# Seeeduino_LoRaWan.net
KiCad netlist of a schematic drawn in EAGLE
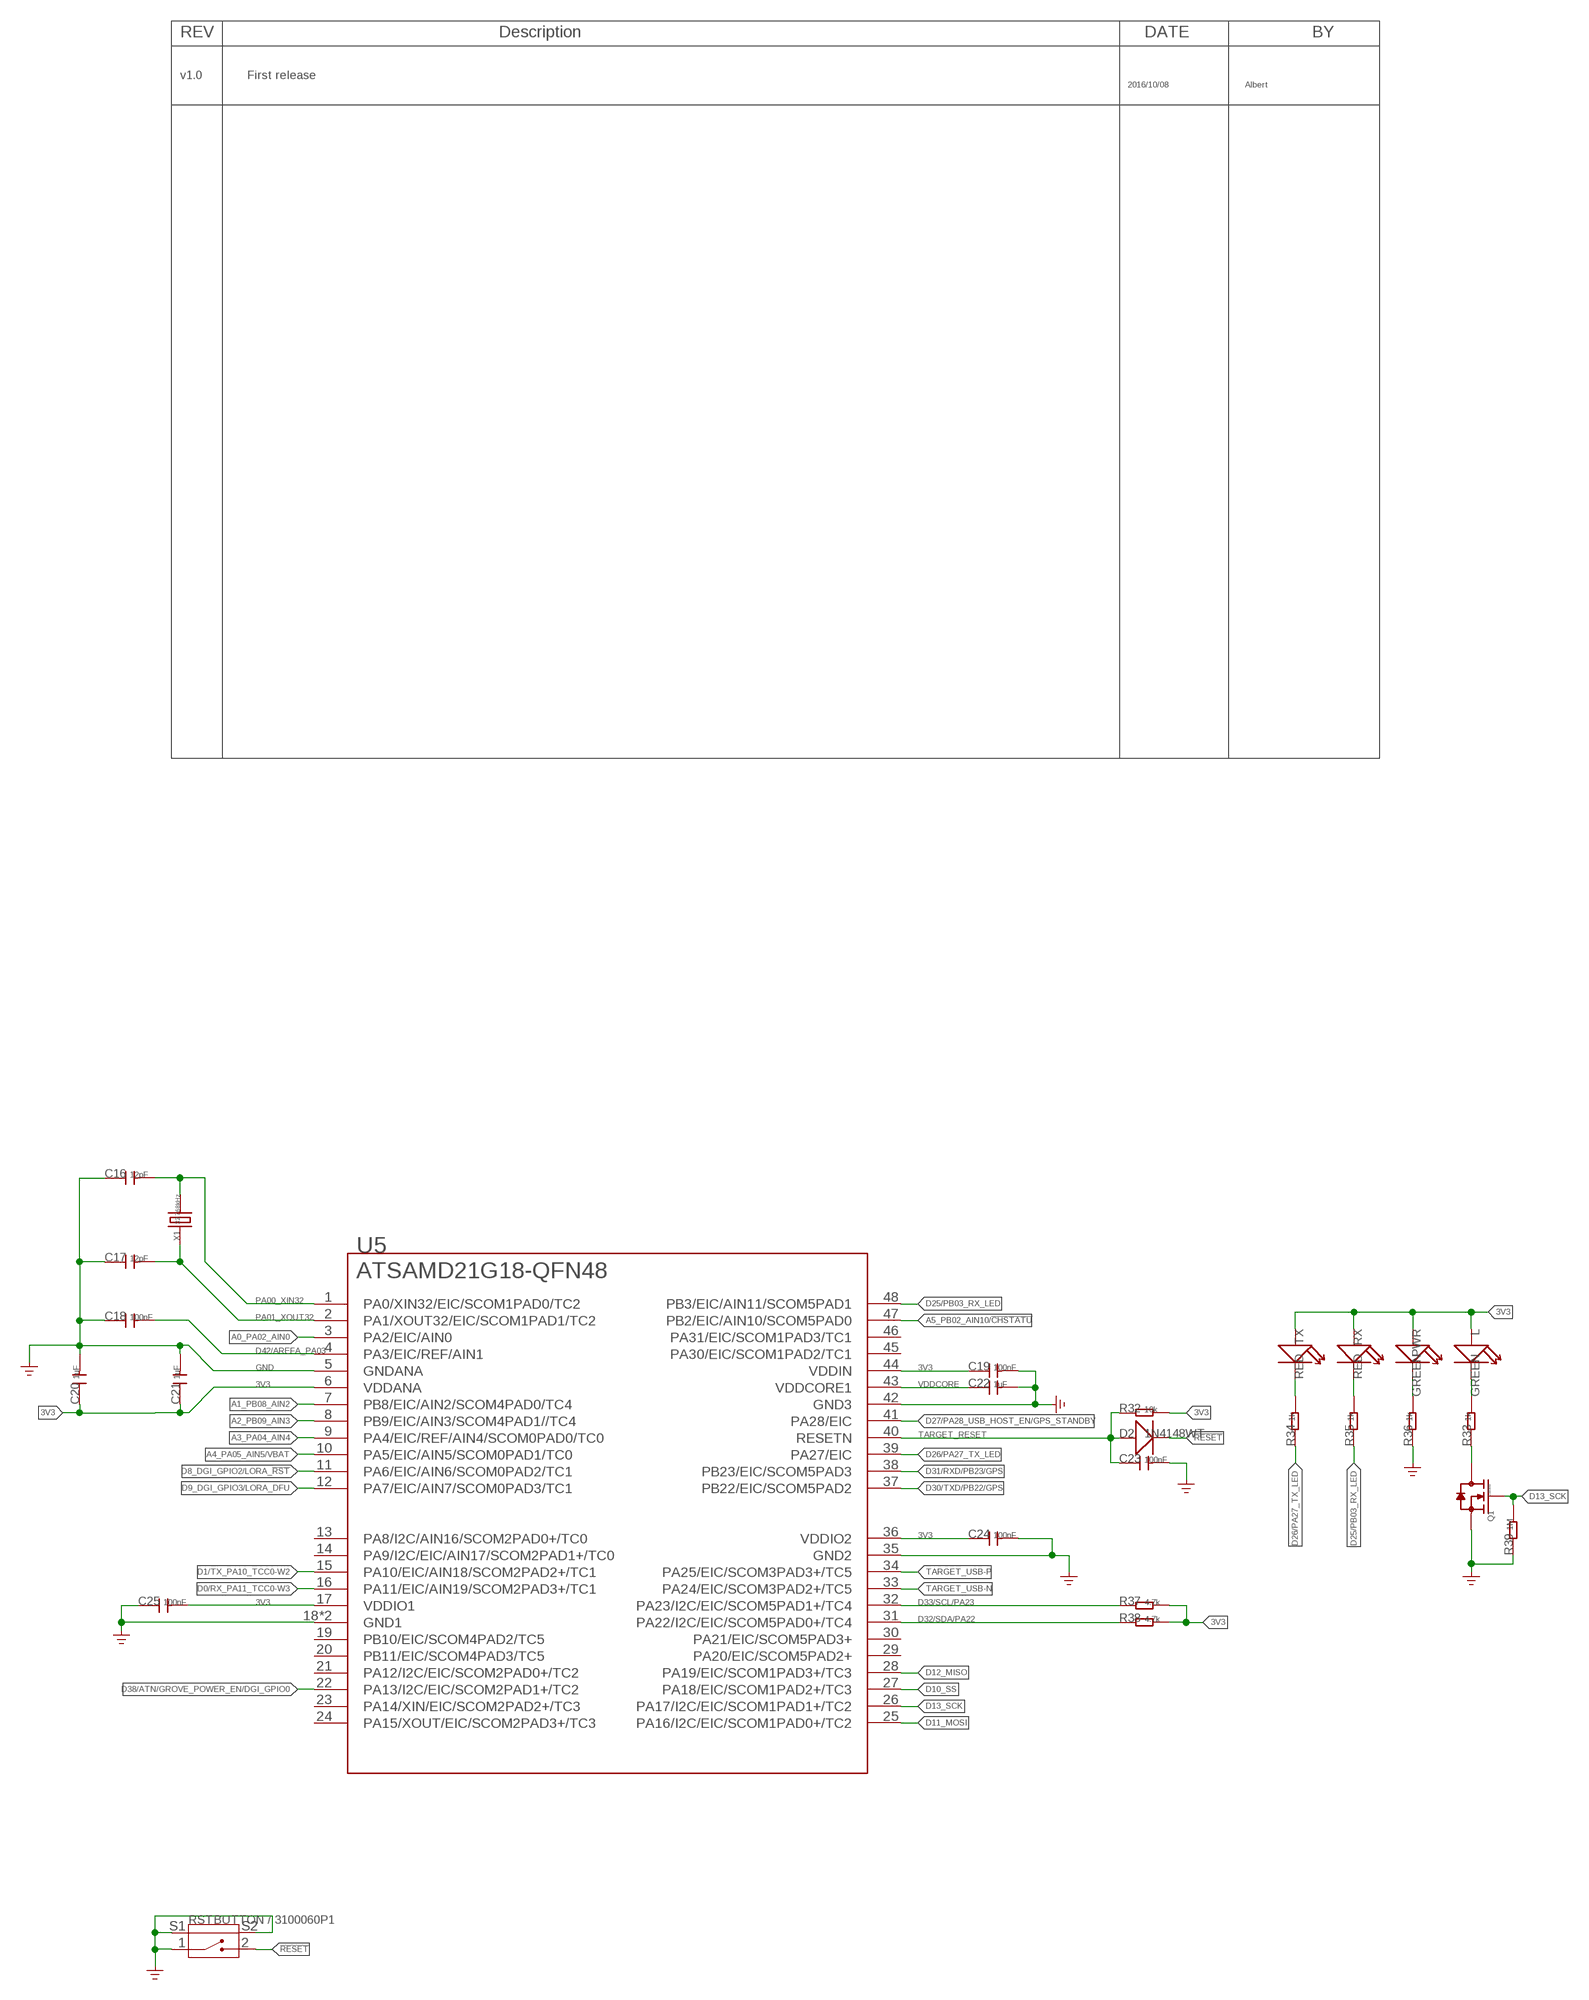
[diagram p0: schematic, sheet 1, part 1 of 2]
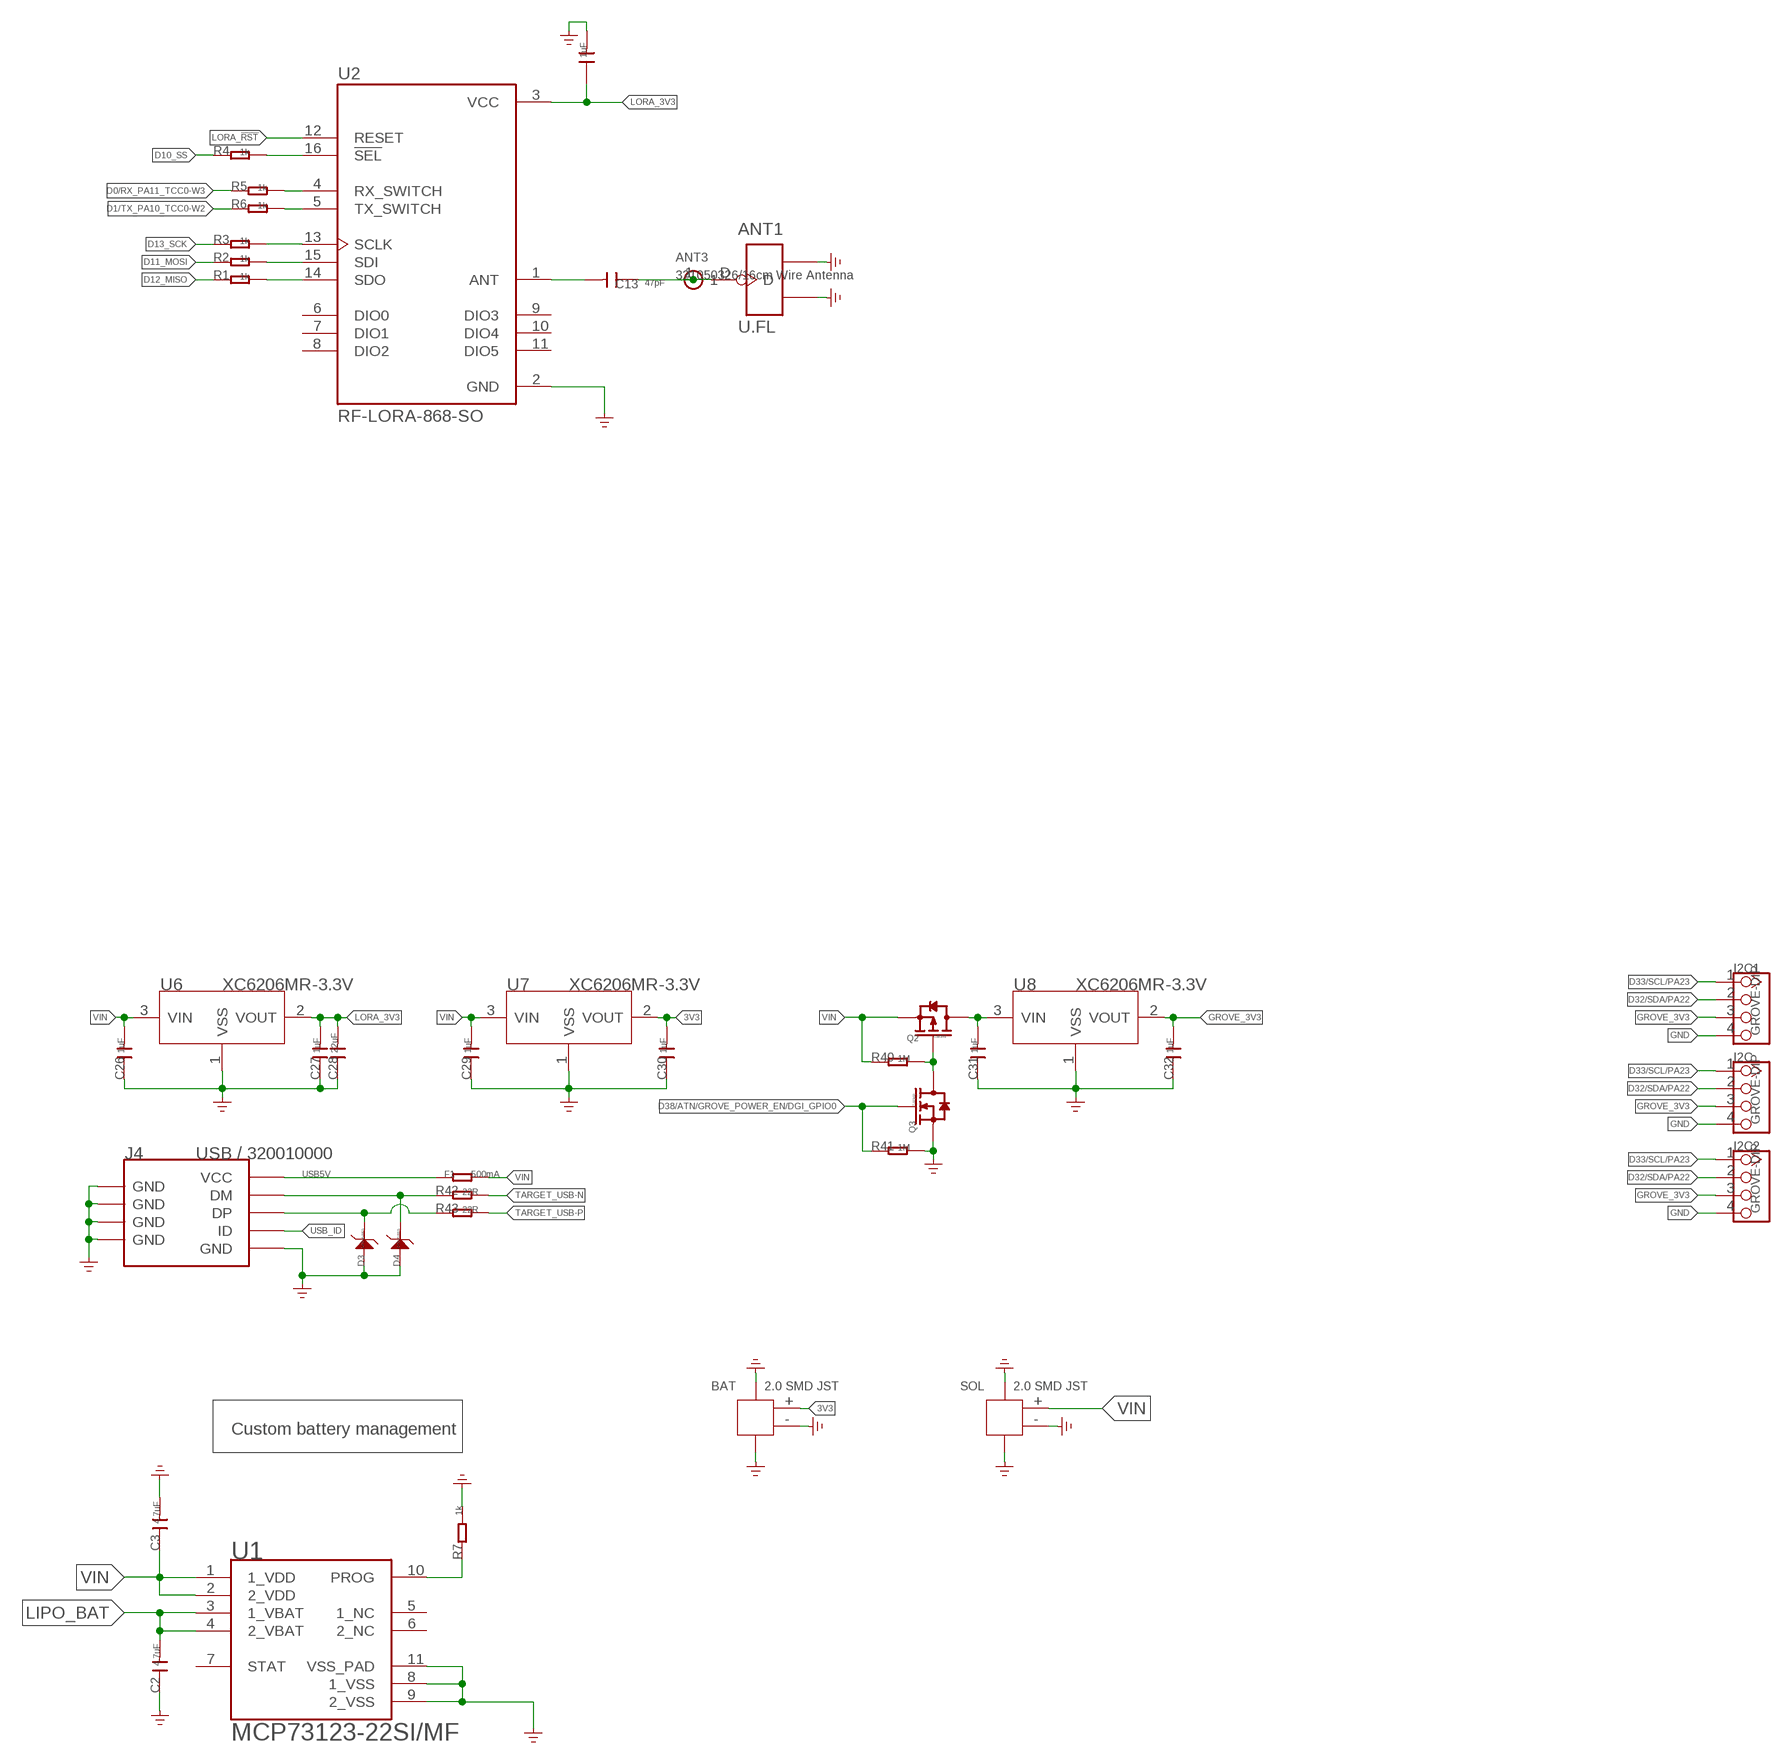
[diagram p1: schematic, sheet 1, part 2 of 2]

(export (version "E")
  (design (tool "Eeschema 10.0.6"))
  (components
    (comp (ref "ANT1")
      (value "U.FL")
      (footprint "eagle-import:U-FL3P-SMD-2.6X2.6X1.0MM")
      (libsource (lib "eagle-import") (part "ANTENNA-U-FL"))
    )
    (comp (ref "ANT3")
      (value "321050326/16cm Wire Antenna")
      (footprint "eagle-import:1P-65_35MIL")
      (libsource (lib "eagle-import") (part "HEADER-1P-35"))
    )
    (comp (ref "BAT")
      (value "2.0 SMD JST")
      (footprint "eagle-import:HW2-SMD-2.0-90D")
      (libsource (lib "eagle-import") (part "JST-2P-SMD'2.0'"))
    )
    (comp (ref "C1")
      (value "1uF")
      (footprint "eagle-import:C0603")
      (libsource (lib "eagle-import") (part "C-0603"))
    )
    (comp (ref "C2")
      (value "4.7uF")
      (footprint "eagle-import:C0603")
      (libsource (lib "eagle-import") (part "C-0603"))
    )
    (comp (ref "C3")
      (value "4.7uF")
      (footprint "eagle-import:C0603")
      (libsource (lib "eagle-import") (part "C-0603"))
    )
    (comp (ref "C13")
      (value "47pF")
      (footprint "eagle-import:C0603")
      (libsource (lib "eagle-import") (part "C-0603"))
    )
    (comp (ref "C16")
      (value "12pF")
      (footprint "eagle-import:C0603")
      (libsource (lib "eagle-import") (part "C-0603"))
    )
    (comp (ref "C17")
      (value "12pF")
      (footprint "eagle-import:C0603")
      (libsource (lib "eagle-import") (part "C-0603"))
    )
    (comp (ref "C18")
      (value "100nF")
      (footprint "eagle-import:C0603")
      (libsource (lib "eagle-import") (part "C-0603"))
    )
    (comp (ref "C19")
      (value "100nF")
      (footprint "eagle-import:C0603")
      (libsource (lib "eagle-import") (part "C-0603"))
    )
    (comp (ref "C20")
      (value "1uF")
      (footprint "eagle-import:C0603")
      (libsource (lib "eagle-import") (part "C-0603"))
    )
    (comp (ref "C21")
      (value "1uF")
      (footprint "eagle-import:C0603")
      (libsource (lib "eagle-import") (part "C-0603"))
    )
    (comp (ref "C22")
      (value "1uF")
      (footprint "eagle-import:C0603")
      (libsource (lib "eagle-import") (part "C-0603"))
    )
    (comp (ref "C23")
      (value "100nF")
      (footprint "eagle-import:C0603")
      (libsource (lib "eagle-import") (part "C-0603"))
    )
    (comp (ref "C24")
      (value "100nF")
      (footprint "eagle-import:C0603")
      (libsource (lib "eagle-import") (part "C-0603"))
    )
    (comp (ref "C25")
      (value "100nF")
      (footprint "eagle-import:C0603")
      (libsource (lib "eagle-import") (part "C-0603"))
    )
    (comp (ref "C26")
      (value "1uF")
      (footprint "eagle-import:C0603")
      (libsource (lib "eagle-import") (part "C-0603"))
    )
    (comp (ref "C27")
      (value "1uF")
      (footprint "eagle-import:C0603")
      (libsource (lib "eagle-import") (part "C-0603"))
    )
    (comp (ref "C28")
      (value "22uF")
      (footprint "eagle-import:C0603")
      (libsource (lib "eagle-import") (part "C-0603"))
    )
    (comp (ref "C29")
      (value "1uF")
      (footprint "eagle-import:C0603")
      (libsource (lib "eagle-import") (part "C-0603"))
    )
    (comp (ref "C30")
      (value "1uF")
      (footprint "eagle-import:C0603")
      (libsource (lib "eagle-import") (part "C-0603"))
    )
    (comp (ref "C31")
      (value "1uF")
      (footprint "eagle-import:C0603")
      (libsource (lib "eagle-import") (part "C-0603"))
    )
    (comp (ref "C32")
      (value "1uF")
      (footprint "eagle-import:C0603")
      (libsource (lib "eagle-import") (part "C-0603"))
    )
    (comp (ref "D2")
      (value "1N4148WT")
      (footprint "eagle-import:SOD523")
      (libsource (lib "eagle-import") (part "D'0603'"))
    )
    (comp (ref "D3")
      (value "DF2S6.8FS")
      (footprint "eagle-import:SOD-923")
      (libsource (lib "eagle-import") (part "D-ESD-2P'DF2S6.8FS'"))
    )
    (comp (ref "D4")
      (value "DF2S6.8FS")
      (footprint "eagle-import:SOD-923")
      (libsource (lib "eagle-import") (part "D-ESD-2P'DF2S6.8FS'"))
    )
    (comp (ref "F1")
      (value "500mA")
      (footprint "eagle-import:R0603")
      (libsource (lib "eagle-import") (part "Discrete-smallsmall_R-0603"))
    )
    (comp (ref "I2C")
      (value "GROVE-DIP")
      (footprint "eagle-import:4P-2.0")
      (libsource (lib "eagle-import") (part "TWIG-4P-2.0-2.0"))
    )
    (comp (ref "I2C1")
      (value "GROVE-DIP")
      (footprint "eagle-import:4P-2.0")
      (libsource (lib "eagle-import") (part "TWIG-4P-2.0-2.0"))
    )
    (comp (ref "I2C2")
      (value "GROVE-DIP")
      (footprint "eagle-import:4P-2.0")
      (libsource (lib "eagle-import") (part "TWIG-4P-2.0-2.0"))
    )
    (comp (ref "J4")
      (value "USB / 320010000")
      (footprint "eagle-import:MICRO-USB")
      (libsource (lib "eagle-import") (part "USB-MINIUSB-5P-MICRO"))
    )
    (comp (ref "L")
      (value "GREEN")
      (footprint "eagle-import:LED-0603")
      (libsource (lib "eagle-import") (part "LED'0603'"))
    )
    (comp (ref "PWR")
      (value "GREEN")
      (footprint "eagle-import:LED-0603")
      (libsource (lib "eagle-import") (part "LED'0603'"))
    )
    (comp (ref "Q1")
      (value "CJ2102")
      (footprint "eagle-import:SOT-323")
      (libsource (lib "eagle-import") (part "MOSFET-N'SI1304BDL'"))
    )
    (comp (ref "Q2")
      (value "CJ2101")
      (footprint "eagle-import:SOT323")
      (libsource (lib "eagle-import") (part "MOSFET-P-SOT323"))
    )
    (comp (ref "Q3")
      (value "CJ2102")
      (footprint "eagle-import:SOT-323")
      (libsource (lib "eagle-import") (part "MOSFET-N'SI1304BDL'"))
    )
    (comp (ref "R1")
      (value "1k")
      (footprint "eagle-import:R0603")
      (libsource (lib "eagle-import") (part "R-0603"))
    )
    (comp (ref "R2")
      (value "1k")
      (footprint "eagle-import:R0603")
      (libsource (lib "eagle-import") (part "R-0603"))
    )
    (comp (ref "R3")
      (value "1k")
      (footprint "eagle-import:R0603")
      (libsource (lib "eagle-import") (part "R-0603"))
    )
    (comp (ref "R4")
      (value "1k")
      (footprint "eagle-import:R0603")
      (libsource (lib "eagle-import") (part "R-0603"))
    )
    (comp (ref "R5")
      (value "1k")
      (footprint "eagle-import:R0603")
      (libsource (lib "eagle-import") (part "R-0603"))
    )
    (comp (ref "R6")
      (value "1k")
      (footprint "eagle-import:R0603")
      (libsource (lib "eagle-import") (part "R-0603"))
    )
    (comp (ref "R7")
      (value "1k")
      (footprint "eagle-import:R0603")
      (libsource (lib "eagle-import") (part "R-0603"))
    )
    (comp (ref "R32")
      (value "10k")
      (footprint "eagle-import:R0603")
      (libsource (lib "eagle-import") (part "R-0603"))
    )
    (comp (ref "R33")
      (value "1k")
      (footprint "eagle-import:R0603")
      (libsource (lib "eagle-import") (part "R-0603"))
    )
    (comp (ref "R34")
      (value "1k")
      (footprint "eagle-import:R0603")
      (libsource (lib "eagle-import") (part "R-0603"))
    )
    (comp (ref "R35")
      (value "1k")
      (footprint "eagle-import:R0603")
      (libsource (lib "eagle-import") (part "R-0603"))
    )
    (comp (ref "R36")
      (value "1k")
      (footprint "eagle-import:R0603")
      (libsource (lib "eagle-import") (part "R-0603"))
    )
    (comp (ref "R37")
      (value "4.7k")
      (footprint "eagle-import:R0603")
      (libsource (lib "eagle-import") (part "R-0603"))
    )
    (comp (ref "R38")
      (value "4.7k")
      (footprint "eagle-import:R0603")
      (libsource (lib "eagle-import") (part "R-0603"))
    )
    (comp (ref "R39")
      (value "1M")
      (footprint "eagle-import:R0603")
      (libsource (lib "eagle-import") (part "R-0603"))
    )
    (comp (ref "R40")
      (value "1M")
      (footprint "eagle-import:R0603")
      (libsource (lib "eagle-import") (part "R-0603"))
    )
    (comp (ref "R41")
      (value "1M")
      (footprint "eagle-import:R0603")
      (libsource (lib "eagle-import") (part "R-0603"))
    )
    (comp (ref "R42")
      (value "22R")
      (footprint "eagle-import:R0603")
      (libsource (lib "eagle-import") (part "R-0603"))
    )
    (comp (ref "R43")
      (value "22R")
      (footprint "eagle-import:R0603")
      (libsource (lib "eagle-import") (part "R-0603"))
    )
    (comp (ref "RST")
      (value "BUTTON / 3100060P1")
      (footprint "eagle-import:4P-SMD-7.0X3.5X3.5H-90D")
      (libsource (lib "eagle-import") (part "BUTTON-2P-REINFORCE-3100060P1"))
    )
    (comp (ref "RX")
      (value "RED")
      (footprint "eagle-import:LED-0603")
      (libsource (lib "eagle-import") (part "LED'0603'"))
    )
    (comp (ref "SOL")
      (value "2.0 SMD JST")
      (footprint "eagle-import:HW2-SMD-2.0-90D")
      (libsource (lib "eagle-import") (part "JST-2P-SMD'2.0'"))
    )
    (comp (ref "TX")
      (value "RED")
      (footprint "eagle-import:LED-0603")
      (libsource (lib "eagle-import") (part "LED'0603'"))
    )
    (comp (ref "U1")
      (value "MICROCHIP_MCP73123-22SI-MFMICROCHIP_MCP73123-22SI-MF_0_0")
      (footprint "eagle-import:MICROCHIP_MCP73123-22SI-MF_0")
      (fields
        (field (name "DIGIKEY_PART_NUMBER") "MCP73123-22SI/MF-ND")
        (field (name "MF") "Microchip")
        (field (name "MOUSER_PART_NUMBER") "579-MCP73123-22SI/MF")
      )
      (libsource (lib "eagle-import") (part "MICROCHIP_MCP73123-22SI-MFMICROCHIP_MCP73123-22SI-MF_0_0"))
    )
    (comp (ref "U2")
      (value "RF-LORA-868-SO")
      (footprint "eagle-import:XCVR_RF-LORA-868-SO")
      (fields (field (name "DIGI-KEY_PART_NUMBER") "RF-LORA-868-SO-ND") (field (name "MF") "RF Solutions"))
      (libsource (lib "eagle-import") (part "RF-LORA-868-SO"))
    )
    (comp (ref "U5")
      (value "ATSAMD21G18-QFN48")
      (footprint "eagle-import:QFN48-7X7")
      (libsource (lib "eagle-import") (part "ATSAMD21G18-QFN48"))
    )
    (comp (ref "U6")
      (value "XC6206MR-3.3V")
      (footprint "eagle-import:SOT23")
      (libsource (lib "eagle-import") (part "XC6206MR"))
    )
    (comp (ref "U7")
      (value "XC6206MR-3.3V")
      (footprint "eagle-import:SOT23")
      (libsource (lib "eagle-import") (part "XC6206MR"))
    )
    (comp (ref "U8")
      (value "XC6206MR-3.3V")
      (footprint "eagle-import:SOT23")
      (libsource (lib "eagle-import") (part "XC6206MR"))
    )
    (comp (ref "X1")
      (value "32.768kHz")
      (footprint "eagle-import:X2-SMD-3.2X1.5X0.55MM")
      (libsource (lib "eagle-import") (part "CRYSTAL-2P-3215"))
    )
  )
  (nets
    (net (code "1") (name "/A5_PB02_AIN10{slash}~{CHSTATU}") (class "Default")
      (node (ref "U5") (pin "47") (pinfunction "PB2/EIC/AIN10/SCOM5PAD0_47") (pintype "bidirectional"))
    )
    (net (code "2") (name "/D8_DGI_GPIO2{slash}LORA_~{RST}") (class "Default")
      (node (ref "U5") (pin "11") (pinfunction "PA6/EIC/AIN6/SCOM0PAD2/TC1_11") (pintype "bidirectional"))
    )
    (net (code "3") (name "/D42{slash}AREFA_PA03") (class "Default")
      (node (ref "C18") (pin "2") (pinfunction "2_2") (pintype "passive"))
      (node (ref "U5") (pin "4") (pinfunction "PA3/EIC/REF/AIN1_4") (pintype "bidirectional"))
    )
    (net (code "4") (name "/LORA_~{RST}") (class "Default")
      (node (ref "U2") (pin "12") (pinfunction "RESET_12") (pintype "input"))
    )
    (net (code "5") (name "/PA00_XIN32") (class "Default")
      (node (ref "C16") (pin "2") (pinfunction "2_2") (pintype "passive"))
      (node (ref "U5") (pin "1") (pinfunction "PA0/XIN32/EIC/SCOM1PAD0/TC2_1") (pintype "bidirectional"))
      (node (ref "X1") (pin "2") (pinfunction "2_2") (pintype "passive"))
    )
    (net (code "6") (name "/PA01_XOUT32") (class "Default")
      (node (ref "C17") (pin "2") (pinfunction "2_2") (pintype "passive"))
      (node (ref "U5") (pin "2") (pinfunction "PA1/XOUT32/EIC/SCOM1PAD1/TC2_2") (pintype "bidirectional"))
      (node (ref "X1") (pin "1") (pinfunction "1_1") (pintype "passive"))
    )
    (net (code "7") (name "/TARGET_RESET") (class "Default")
      (node (ref "C23") (pin "1") (pinfunction "1_1") (pintype "passive"))
      (node (ref "D2") (pin "+") (pinfunction "+_+") (pintype "passive"))
      (node (ref "R32") (pin "1") (pinfunction "1_1") (pintype "passive"))
      (node (ref "U5") (pin "40") (pinfunction "RESETN_40") (pintype "bidirectional"))
    )
    (net (code "8") (name "/USB5V") (class "Default")
      (node (ref "F1") (pin "1") (pinfunction "1_1") (pintype "passive"))
      (node (ref "J4") (pin "1") (pinfunction "VCC_1") (pintype "bidirectional"))
    )
    (net (code "9") (name "/VDDCORE") (class "Default")
      (node (ref "C22") (pin "1") (pinfunction "1_1") (pintype "passive"))
      (node (ref "U5") (pin "43") (pinfunction "VDDCORE1_43") (pintype "input"))
    )
    (net (code "10") (name "/~{RESET}") (class "Default")
      (node (ref "D2") (pin "-") (pinfunction "-_-") (pintype "passive"))
      (node (ref "RST") (pin "2") (pinfunction "2_2") (pintype "bidirectional"))
    )
    (net (code "11") (name "3V3") (class "Default")
      (node (ref "BAT") (pin "+") (pinfunction "1_+") (pintype "bidirectional"))
      (node (ref "C19") (pin "1") (pinfunction "1_1") (pintype "passive"))
      (node (ref "C20") (pin "1") (pinfunction "1_1") (pintype "passive"))
      (node (ref "C21") (pin "1") (pinfunction "1_1") (pintype "passive"))
      (node (ref "C24") (pin "1") (pinfunction "1_1") (pintype "passive"))
      (node (ref "C25") (pin "2") (pinfunction "2_2") (pintype "passive"))
      (node (ref "C30") (pin "2") (pinfunction "2_2") (pintype "passive"))
      (node (ref "L") (pin "+") (pinfunction "+_+") (pintype "passive"))
      (node (ref "PWR") (pin "+") (pinfunction "+_+") (pintype "passive"))
      (node (ref "R32") (pin "2") (pinfunction "2_2") (pintype "passive"))
      (node (ref "R37") (pin "2") (pinfunction "2_2") (pintype "passive"))
      (node (ref "R38") (pin "2") (pinfunction "2_2") (pintype "passive"))
      (node (ref "RX") (pin "+") (pinfunction "+_+") (pintype "passive"))
      (node (ref "TX") (pin "+") (pinfunction "+_+") (pintype "passive"))
      (node (ref "U5") (pin "17") (pinfunction "VDDIO1_17") (pintype "power_in"))
      (node (ref "U5") (pin "36") (pinfunction "VDDIO2_36") (pintype "power_in"))
      (node (ref "U5") (pin "44") (pinfunction "VDDIN_44") (pintype "power_in"))
      (node (ref "U5") (pin "6") (pinfunction "VDDANA_6") (pintype "power_in"))
      (node (ref "U7") (pin "2") (pinfunction "VOUT_2") (pintype "output"))
    )
    (net (code "12") (name "A0_PA02_AIN0") (class "Default")
      (node (ref "U5") (pin "3") (pinfunction "PA2/EIC/AIN0_3") (pintype "bidirectional"))
    )
    (net (code "13") (name "A1_PB08_AIN2") (class "Default")
      (node (ref "U5") (pin "7") (pinfunction "PB8/EIC/AIN2/SCOM4PAD0/TC4_7") (pintype "bidirectional"))
    )
    (net (code "14") (name "A2_PB09_AIN3") (class "Default")
      (node (ref "U5") (pin "8") (pinfunction "PB9/EIC/AIN3/SCOM4PAD1//TC4_8") (pintype "bidirectional"))
    )
    (net (code "15") (name "A3_PA04_AIN4") (class "Default")
      (node (ref "U5") (pin "9") (pinfunction "PA4/EIC/REF/AIN4/SCOM0PAD0/TC0_9") (pintype "bidirectional"))
    )
    (net (code "16") (name "A4_PA05_AIN5{slash}VBAT") (class "Default")
      (node (ref "U5") (pin "10") (pinfunction "PA5/EIC/AIN5/SCOM0PAD1/TC0_10") (pintype "bidirectional"))
    )
    (net (code "17") (name "D0{slash}RX_PA11_TCC0-W3") (class "Default")
      (node (ref "R5") (pin "1") (pinfunction "1_1") (pintype "passive"))
      (node (ref "U5") (pin "16") (pinfunction "PA11/EIC/AIN19/SCOM2PAD3+/TC1_16") (pintype "bidirectional"))
    )
    (net (code "18") (name "D1{slash}TX_PA10_TCC0-W2") (class "Default")
      (node (ref "R6") (pin "1") (pinfunction "1_1") (pintype "passive"))
      (node (ref "U5") (pin "15") (pinfunction "PA10/EIC/AIN18/SCOM2PAD2+/TC1_15") (pintype "bidirectional"))
    )
    (net (code "19") (name "D9_DGI_GPIO3{slash}LORA_DFU") (class "Default")
      (node (ref "U5") (pin "12") (pinfunction "PA7/EIC/AIN7/SCOM0PAD3/TC1_12") (pintype "bidirectional"))
    )
    (net (code "20") (name "D10_SS") (class "Default")
      (node (ref "R4") (pin "1") (pinfunction "1_1") (pintype "passive"))
      (node (ref "U5") (pin "27") (pinfunction "PA18/EIC/SCOM1PAD2+/TC3_27") (pintype "bidirectional"))
    )
    (net (code "21") (name "D11_MOSI") (class "Default")
      (node (ref "R2") (pin "1") (pinfunction "1_1") (pintype "passive"))
      (node (ref "U5") (pin "25") (pinfunction "PA16/I2C/EIC/SCOM1PAD0+/TC2_25") (pintype "bidirectional"))
    )
    (net (code "22") (name "D12_MISO") (class "Default")
      (node (ref "R1") (pin "1") (pinfunction "1_1") (pintype "passive"))
      (node (ref "U5") (pin "28") (pinfunction "PA19/EIC/SCOM1PAD3+/TC3_28") (pintype "bidirectional"))
    )
    (net (code "23") (name "D13_SCK") (class "Default")
      (node (ref "Q1") (pin "1") (pinfunction "G_1") (pintype "passive"))
      (node (ref "R3") (pin "1") (pinfunction "1_1") (pintype "passive"))
      (node (ref "R39") (pin "2") (pinfunction "2_2") (pintype "passive"))
      (node (ref "U5") (pin "26") (pinfunction "PA17/I2C/EIC/SCOM1PAD1+/TC2_26") (pintype "bidirectional"))
    )
    (net (code "24") (name "D25{slash}PB03_RX_LED") (class "Default")
      (node (ref "R35") (pin "1") (pinfunction "1_1") (pintype "passive"))
      (node (ref "U5") (pin "48") (pinfunction "PB3/EIC/AIN11/SCOM5PAD1_48") (pintype "bidirectional"))
    )
    (net (code "25") (name "D26{slash}PA27_TX_LED") (class "Default")
      (node (ref "R34") (pin "1") (pinfunction "1_1") (pintype "passive"))
      (node (ref "U5") (pin "39") (pinfunction "PA27/EIC_39") (pintype "bidirectional"))
    )
    (net (code "26") (name "D27{slash}PA28_USB_HOST_EN{slash}GPS_STANDBY") (class "Default")
      (node (ref "U5") (pin "41") (pinfunction "PA28/EIC_41") (pintype "bidirectional"))
    )
    (net (code "27") (name "D30{slash}TXD{slash}PB22{slash}GPS") (class "Default")
      (node (ref "U5") (pin "37") (pinfunction "PB22/EIC/SCOM5PAD2_37") (pintype "bidirectional"))
    )
    (net (code "28") (name "D31{slash}RXD{slash}PB23{slash}GPS") (class "Default")
      (node (ref "U5") (pin "38") (pinfunction "PB23/EIC/SCOM5PAD3_38") (pintype "bidirectional"))
    )
    (net (code "29") (name "D32{slash}SDA{slash}PA22") (class "Default")
      (node (ref "I2C") (pin "2") (pinfunction "2_2") (pintype "bidirectional"))
      (node (ref "I2C1") (pin "2") (pinfunction "2_2") (pintype "bidirectional"))
      (node (ref "I2C2") (pin "2") (pinfunction "2_2") (pintype "bidirectional"))
      (node (ref "R38") (pin "1") (pinfunction "1_1") (pintype "passive"))
      (node (ref "U5") (pin "31") (pinfunction "PA22/I2C/EIC/SCOM5PAD0+/TC4_31") (pintype "bidirectional"))
    )
    (net (code "30") (name "D33{slash}SCL{slash}PA23") (class "Default")
      (node (ref "I2C") (pin "1") (pinfunction "1_1") (pintype "bidirectional"))
      (node (ref "I2C1") (pin "1") (pinfunction "1_1") (pintype "bidirectional"))
      (node (ref "I2C2") (pin "1") (pinfunction "1_1") (pintype "bidirectional"))
      (node (ref "R37") (pin "1") (pinfunction "1_1") (pintype "passive"))
      (node (ref "U5") (pin "32") (pinfunction "PA23/I2C/EIC/SCOM5PAD1+/TC4_32") (pintype "bidirectional"))
    )
    (net (code "31") (name "D38{slash}ATN{slash}GROVE_POWER_EN{slash}DGI_GPIO0") (class "Default")
      (node (ref "Q3") (pin "1") (pinfunction "G_1") (pintype "passive"))
      (node (ref "R41") (pin "1") (pinfunction "1_1") (pintype "passive"))
      (node (ref "U5") (pin "22") (pinfunction "PA13/I2C/EIC/SCOM2PAD1+/TC2_22") (pintype "bidirectional"))
    )
    (net (code "32") (name "GND") (class "Default")
      (node (ref "ANT1") (pin "GND1") (pinfunction "GND1_GND1") (pintype "bidirectional"))
      (node (ref "ANT1") (pin "GND2") (pinfunction "GND2_GND2") (pintype "bidirectional"))
      (node (ref "BAT") (pin "-") (pinfunction "2_-") (pintype "bidirectional"))
      (node (ref "BAT") (pin "3") (pinfunction "3_3") (pintype "bidirectional"))
      (node (ref "BAT") (pin "4") (pinfunction "4_4") (pintype "bidirectional"))
      (node (ref "C1") (pin "2") (pinfunction "2_2") (pintype "passive"))
      (node (ref "C16") (pin "1") (pinfunction "1_1") (pintype "passive"))
      (node (ref "C17") (pin "1") (pinfunction "1_1") (pintype "passive"))
      (node (ref "C18") (pin "1") (pinfunction "1_1") (pintype "passive"))
      (node (ref "C19") (pin "2") (pinfunction "2_2") (pintype "passive"))
      (node (ref "C2") (pin "1") (pinfunction "1_1") (pintype "passive"))
      (node (ref "C20") (pin "2") (pinfunction "2_2") (pintype "passive"))
      (node (ref "C21") (pin "2") (pinfunction "2_2") (pintype "passive"))
      (node (ref "C22") (pin "2") (pinfunction "2_2") (pintype "passive"))
      (node (ref "C23") (pin "2") (pinfunction "2_2") (pintype "passive"))
      (node (ref "C24") (pin "2") (pinfunction "2_2") (pintype "passive"))
      (node (ref "C25") (pin "1") (pinfunction "1_1") (pintype "passive"))
      (node (ref "C26") (pin "1") (pinfunction "1_1") (pintype "passive"))
      (node (ref "C27") (pin "1") (pinfunction "1_1") (pintype "passive"))
      (node (ref "C28") (pin "1") (pinfunction "1_1") (pintype "passive"))
      (node (ref "C29") (pin "1") (pinfunction "1_1") (pintype "passive"))
      (node (ref "C3") (pin "2") (pinfunction "2_2") (pintype "passive"))
      (node (ref "C30") (pin "1") (pinfunction "1_1") (pintype "passive"))
      (node (ref "C31") (pin "1") (pinfunction "1_1") (pintype "passive"))
      (node (ref "C32") (pin "1") (pinfunction "1_1") (pintype "passive"))
      (node (ref "D3") (pin "2") (pinfunction "1_2") (pintype "bidirectional"))
      (node (ref "D4") (pin "2") (pinfunction "1_2") (pintype "bidirectional"))
      (node (ref "I2C") (pin "4") (pinfunction "4_4") (pintype "bidirectional"))
      (node (ref "I2C1") (pin "4") (pinfunction "4_4") (pintype "bidirectional"))
      (node (ref "I2C2") (pin "4") (pinfunction "4_4") (pintype "bidirectional"))
      (node (ref "J4") (pin "5") (pinfunction "GND_5") (pintype "bidirectional"))
      (node (ref "J4") (pin "S1") (pinfunction "GND_S1") (pintype "bidirectional"))
      (node (ref "J4") (pin "S2") (pinfunction "GND_S2") (pintype "bidirectional"))
      (node (ref "J4") (pin "S3") (pinfunction "GND_S3") (pintype "bidirectional"))
      (node (ref "J4") (pin "S4") (pinfunction "GND_S4") (pintype "bidirectional"))
      (node (ref "J4") (pin "S5") (pinfunction "GND_S5") (pintype "bidirectional"))
      (node (ref "J4") (pin "S6") (pinfunction "GND_S6") (pintype "bidirectional"))
      (node (ref "Q1") (pin "2") (pinfunction "S_2") (pintype "passive"))
      (node (ref "Q3") (pin "2") (pinfunction "S_2") (pintype "passive"))
      (node (ref "R36") (pin "1") (pinfunction "1_1") (pintype "passive"))
      (node (ref "R39") (pin "1") (pinfunction "1_1") (pintype "passive"))
      (node (ref "R41") (pin "2") (pinfunction "2_2") (pintype "passive"))
      (node (ref "R7") (pin "2") (pinfunction "2_2") (pintype "passive"))
      (node (ref "RST") (pin "1") (pinfunction "1_1") (pintype "bidirectional"))
      (node (ref "RST") (pin "S1") (pinfunction "S1_S1") (pintype "bidirectional"))
      (node (ref "RST") (pin "S2") (pinfunction "S2_S2") (pintype "bidirectional"))
      (node (ref "SOL") (pin "-") (pinfunction "2_-") (pintype "bidirectional"))
      (node (ref "SOL") (pin "3") (pinfunction "3_3") (pintype "bidirectional"))
      (node (ref "SOL") (pin "4") (pinfunction "4_4") (pintype "bidirectional"))
      (node (ref "U1") (pin "11") (pinfunction "VSS_PAD_11") (pintype "bidirectional"))
      (node (ref "U1") (pin "8") (pinfunction "1_VSS_8") (pintype "bidirectional"))
      (node (ref "U1") (pin "9") (pinfunction "2_VSS_9") (pintype "bidirectional"))
      (node (ref "U2") (pin "2") (pinfunction "GND_2") (pintype "power_in"))
      (node (ref "U5") (pin "18") (pinfunction "GND1_18") (pintype "power_in"))
      (node (ref "U5") (pin "35") (pinfunction "GND2_35") (pintype "power_in"))
      (node (ref "U5") (pin "42") (pinfunction "GND3_42") (pintype "power_in"))
      (node (ref "U5") (pin "5") (pinfunction "GNDANA_5") (pintype "power_in"))
      (node (ref "U5") (pin "PAD") (pinfunction "GND1_PAD") (pintype "power_in"))
      (node (ref "U6") (pin "1") (pinfunction "VSS_1") (pintype "power_in"))
      (node (ref "U7") (pin "1") (pinfunction "VSS_1") (pintype "power_in"))
      (node (ref "U8") (pin "1") (pinfunction "VSS_1") (pintype "power_in"))
    )
    (net (code "33") (name "GROVE_3V3") (class "Default")
      (node (ref "C32") (pin "2") (pinfunction "2_2") (pintype "passive"))
      (node (ref "I2C") (pin "3") (pinfunction "3_3") (pintype "bidirectional"))
      (node (ref "I2C1") (pin "3") (pinfunction "3_3") (pintype "bidirectional"))
      (node (ref "I2C2") (pin "3") (pinfunction "3_3") (pintype "bidirectional"))
      (node (ref "U8") (pin "2") (pinfunction "VOUT_2") (pintype "output"))
    )
    (net (code "34") (name "LIPO_BAT") (class "Default")
      (node (ref "C2") (pin "2") (pinfunction "2_2") (pintype "passive"))
      (node (ref "U1") (pin "3") (pinfunction "1_VBAT_3") (pintype "bidirectional"))
      (node (ref "U1") (pin "4") (pinfunction "2_VBAT_4") (pintype "bidirectional"))
    )
    (net (code "35") (name "LORA_3V3") (class "Default")
      (node (ref "C1") (pin "1") (pinfunction "1_1") (pintype "passive"))
      (node (ref "C27") (pin "2") (pinfunction "2_2") (pintype "passive"))
      (node (ref "C28") (pin "2") (pinfunction "2_2") (pintype "passive"))
      (node (ref "U2") (pin "3") (pinfunction "VCC_3") (pintype "power_in"))
      (node (ref "U6") (pin "2") (pinfunction "VOUT_2") (pintype "output"))
    )
    (net (code "36") (name "Net-(ANT1-PadD)") (class "Default")
      (node (ref "ANT1") (pin "D") (pinfunction "D_D") (pintype "bidirectional"))
      (node (ref "ANT3") (pin "1") (pinfunction "1_1") (pintype "bidirectional"))
      (node (ref "C13") (pin "1") (pinfunction "1_1") (pintype "passive"))
    )
    (net (code "37") (name "Net-(D3-2)") (class "Default")
      (node (ref "D3") (pin "1") (pinfunction "2_1") (pintype "bidirectional"))
      (node (ref "J4") (pin "3") (pinfunction "DP_3") (pintype "bidirectional"))
      (node (ref "R43") (pin "1") (pinfunction "1_1") (pintype "passive"))
    )
    (net (code "38") (name "Net-(D4-2)") (class "Default")
      (node (ref "D4") (pin "1") (pinfunction "2_1") (pintype "bidirectional"))
      (node (ref "J4") (pin "2") (pinfunction "DM_2") (pintype "bidirectional"))
      (node (ref "R42") (pin "1") (pinfunction "1_1") (pintype "passive"))
    )
    (net (code "39") (name "Net-(L-Pad-)") (class "Default")
      (node (ref "L") (pin "-") (pinfunction "-_-") (pintype "passive"))
      (node (ref "R33") (pin "2") (pinfunction "2_2") (pintype "passive"))
    )
    (net (code "40") (name "Net-(PWR-Pad-)") (class "Default")
      (node (ref "PWR") (pin "-") (pinfunction "-_-") (pintype "passive"))
      (node (ref "R36") (pin "2") (pinfunction "2_2") (pintype "passive"))
    )
    (net (code "41") (name "Net-(Q1-D)") (class "Default")
      (node (ref "Q1") (pin "3") (pinfunction "D_3") (pintype "passive"))
      (node (ref "R33") (pin "1") (pinfunction "1_1") (pintype "passive"))
    )
    (net (code "42") (name "Net-(Q2-D)") (class "Default")
      (node (ref "C31") (pin "2") (pinfunction "2_2") (pintype "passive"))
      (node (ref "Q2") (pin "3") (pinfunction "D_3") (pintype "passive"))
      (node (ref "U8") (pin "3") (pinfunction "VIN_3") (pintype "input"))
    )
    (net (code "43") (name "Net-(Q2-G)") (class "Default")
      (node (ref "Q2") (pin "1") (pinfunction "G_1") (pintype "passive"))
      (node (ref "Q3") (pin "3") (pinfunction "D_3") (pintype "passive"))
      (node (ref "R40") (pin "2") (pinfunction "2_2") (pintype "passive"))
    )
    (net (code "44") (name "Net-(R34-Pad2)") (class "Default")
      (node (ref "R34") (pin "2") (pinfunction "2_2") (pintype "passive"))
      (node (ref "TX") (pin "-") (pinfunction "-_-") (pintype "passive"))
    )
    (net (code "45") (name "Net-(R35-Pad2)") (class "Default")
      (node (ref "R35") (pin "2") (pinfunction "2_2") (pintype "passive"))
      (node (ref "RX") (pin "-") (pinfunction "-_-") (pintype "passive"))
    )
    (net (code "46") (name "Net-(U1-PROG)") (class "Default")
      (node (ref "R7") (pin "1") (pinfunction "1_1") (pintype "passive"))
      (node (ref "U1") (pin "10") (pinfunction "PROG_10") (pintype "bidirectional"))
    )
    (net (code "47") (name "Net-(U2-ANT)") (class "Default")
      (node (ref "C13") (pin "2") (pinfunction "2_2") (pintype "passive"))
      (node (ref "U2") (pin "1") (pinfunction "ANT_1") (pintype "bidirectional"))
    )
    (net (code "48") (name "Net-(U2-RX_SWITCH)") (class "Default")
      (node (ref "R5") (pin "2") (pinfunction "2_2") (pintype "passive"))
      (node (ref "U2") (pin "4") (pinfunction "RX_SWITCH_4") (pintype "input"))
    )
    (net (code "49") (name "Net-(U2-SCLK)") (class "Default")
      (node (ref "R3") (pin "2") (pinfunction "2_2") (pintype "passive"))
      (node (ref "U2") (pin "13") (pinfunction "SCLK_13") (pintype "input"))
    )
    (net (code "50") (name "Net-(U2-SDI)") (class "Default")
      (node (ref "R2") (pin "2") (pinfunction "2_2") (pintype "passive"))
      (node (ref "U2") (pin "15") (pinfunction "SDI_15") (pintype "input"))
    )
    (net (code "51") (name "Net-(U2-SDO)") (class "Default")
      (node (ref "R1") (pin "2") (pinfunction "2_2") (pintype "passive"))
      (node (ref "U2") (pin "14") (pinfunction "SDO_14") (pintype "output"))
    )
    (net (code "52") (name "Net-(U2-TX_SWITCH)") (class "Default")
      (node (ref "R6") (pin "2") (pinfunction "2_2") (pintype "passive"))
      (node (ref "U2") (pin "5") (pinfunction "TX_SWITCH_5") (pintype "input"))
    )
    (net (code "53") (name "Net-(U2-~{SEL})") (class "Default")
      (node (ref "R4") (pin "2") (pinfunction "2_2") (pintype "passive"))
      (node (ref "U2") (pin "16") (pinfunction "~{SEL}_16") (pintype "input"))
    )
    (net (code "54") (name "TARGET_USB-N") (class "Default")
      (node (ref "R42") (pin "2") (pinfunction "2_2") (pintype "passive"))
      (node (ref "U5") (pin "33") (pinfunction "PA24/EIC/SCOM3PAD2+/TC5_33") (pintype "bidirectional"))
    )
    (net (code "55") (name "TARGET_USB-P") (class "Default")
      (node (ref "R43") (pin "2") (pinfunction "2_2") (pintype "passive"))
      (node (ref "U5") (pin "34") (pinfunction "PA25/EIC/SCOM3PAD3+/TC5_34") (pintype "bidirectional"))
    )
    (net (code "56") (name "USB_ID") (class "Default")
      (node (ref "J4") (pin "4") (pinfunction "ID_4") (pintype "bidirectional"))
    )
    (net (code "57") (name "VIN") (class "Default")
      (node (ref "C26") (pin "2") (pinfunction "2_2") (pintype "passive"))
      (node (ref "C29") (pin "2") (pinfunction "2_2") (pintype "passive"))
      (node (ref "C3") (pin "1") (pinfunction "1_1") (pintype "passive"))
      (node (ref "F1") (pin "2") (pinfunction "2_2") (pintype "passive"))
      (node (ref "Q2") (pin "2") (pinfunction "S_2") (pintype "passive"))
      (node (ref "R40") (pin "1") (pinfunction "1_1") (pintype "passive"))
      (node (ref "SOL") (pin "+") (pinfunction "1_+") (pintype "bidirectional"))
      (node (ref "U1") (pin "1") (pinfunction "1_VDD_1") (pintype "bidirectional"))
      (node (ref "U1") (pin "2") (pinfunction "2_VDD_2") (pintype "bidirectional"))
      (node (ref "U6") (pin "3") (pinfunction "VIN_3") (pintype "input"))
      (node (ref "U7") (pin "3") (pinfunction "VIN_3") (pintype "input"))
    )
    (net (code "58") (name "unconnected-(U1-1_NC-Pad5)") (class "Default")
      (node (ref "U1") (pin "5") (pinfunction "1_NC_5") (pintype "bidirectional"))
    )
    (net (code "59") (name "unconnected-(U1-2_NC-Pad6)") (class "Default")
      (node (ref "U1") (pin "6") (pinfunction "2_NC_6") (pintype "bidirectional"))
    )
    (net (code "60") (name "unconnected-(U1-STAT-Pad7)") (class "Default")
      (node (ref "U1") (pin "7") (pinfunction "STAT_7") (pintype "bidirectional"))
    )
    (net (code "61") (name "unconnected-(U2-DIO0-Pad6)") (class "Default")
      (node (ref "U2") (pin "6") (pinfunction "DIO0_6") (pintype "bidirectional"))
    )
    (net (code "62") (name "unconnected-(U2-DIO1-Pad7)") (class "Default")
      (node (ref "U2") (pin "7") (pinfunction "DIO1_7") (pintype "bidirectional"))
    )
    (net (code "63") (name "unconnected-(U2-DIO2-Pad8)") (class "Default")
      (node (ref "U2") (pin "8") (pinfunction "DIO2_8") (pintype "bidirectional"))
    )
    (net (code "64") (name "unconnected-(U2-DIO3-Pad9)") (class "Default")
      (node (ref "U2") (pin "9") (pinfunction "DIO3_9") (pintype "bidirectional"))
    )
    (net (code "65") (name "unconnected-(U2-DIO4-Pad10)") (class "Default")
      (node (ref "U2") (pin "10") (pinfunction "DIO4_10") (pintype "bidirectional"))
    )
    (net (code "66") (name "unconnected-(U2-DIO5-Pad11)") (class "Default")
      (node (ref "U2") (pin "11") (pinfunction "DIO5_11") (pintype "bidirectional"))
    )
    (net (code "67") (name "unconnected-(U5-PA8{slash}I2C{slash}AIN16{slash}SCOM2PAD0+{slash}TC0-Pad13)") (class "Default")
      (node (ref "U5") (pin "13") (pinfunction "PA8/I2C/AIN16/SCOM2PAD0+/TC0_13") (pintype "bidirectional"))
    )
    (net (code "68") (name "unconnected-(U5-PA9{slash}I2C{slash}EIC{slash}AIN17{slash}SCOM2PAD1+{slash}TC0-Pad14)") (class "Default")
      (node (ref "U5") (pin "14") (pinfunction "PA9/I2C/EIC/AIN17/SCOM2PAD1+/TC0_14") (pintype "bidirectional"))
    )
    (net (code "69") (name "unconnected-(U5-PA12{slash}I2C{slash}EIC{slash}SCOM2PAD0+{slash}TC2-Pad21)") (class "Default")
      (node (ref "U5") (pin "21") (pinfunction "PA12/I2C/EIC/SCOM2PAD0+/TC2_21") (pintype "bidirectional"))
    )
    (net (code "70") (name "unconnected-(U5-PA14{slash}XIN{slash}EIC{slash}SCOM2PAD2+{slash}TC3-Pad23)") (class "Default")
      (node (ref "U5") (pin "23") (pinfunction "PA14/XIN/EIC/SCOM2PAD2+/TC3_23") (pintype "bidirectional"))
    )
    (net (code "71") (name "unconnected-(U5-PA15{slash}XOUT{slash}EIC{slash}SCOM2PAD3+{slash}TC3-Pad24)") (class "Default")
      (node (ref "U5") (pin "24") (pinfunction "PA15/XOUT/EIC/SCOM2PAD3+/TC3_24") (pintype "bidirectional"))
    )
    (net (code "72") (name "unconnected-(U5-PA20{slash}EIC{slash}SCOM5PAD2+-Pad29)") (class "Default")
      (node (ref "U5") (pin "29") (pinfunction "PA20/EIC/SCOM5PAD2+_29") (pintype "bidirectional"))
    )
    (net (code "73") (name "unconnected-(U5-PA21{slash}EIC{slash}SCOM5PAD3+-Pad30)") (class "Default")
      (node (ref "U5") (pin "30") (pinfunction "PA21/EIC/SCOM5PAD3+_30") (pintype "bidirectional"))
    )
    (net (code "74") (name "unconnected-(U5-PA30{slash}EIC{slash}SCOM1PAD2{slash}TC1-Pad45)") (class "Default")
      (node (ref "U5") (pin "45") (pinfunction "PA30/EIC/SCOM1PAD2/TC1_45") (pintype "bidirectional"))
    )
    (net (code "75") (name "unconnected-(U5-PA31{slash}EIC{slash}SCOM1PAD3{slash}TC1-Pad46)") (class "Default")
      (node (ref "U5") (pin "46") (pinfunction "PA31/EIC/SCOM1PAD3/TC1_46") (pintype "bidirectional"))
    )
    (net (code "76") (name "unconnected-(U5-PB10{slash}EIC{slash}SCOM4PAD2{slash}TC5-Pad19)") (class "Default")
      (node (ref "U5") (pin "19") (pinfunction "PB10/EIC/SCOM4PAD2/TC5_19") (pintype "bidirectional"))
    )
    (net (code "77") (name "unconnected-(U5-PB11{slash}EIC{slash}SCOM4PAD3{slash}TC5-Pad20)") (class "Default")
      (node (ref "U5") (pin "20") (pinfunction "PB11/EIC/SCOM4PAD3/TC5_20") (pintype "bidirectional"))
    )
  )
)
